# Power_Supply.net
KiCad netlist of a schematic drawn in Altium Designer
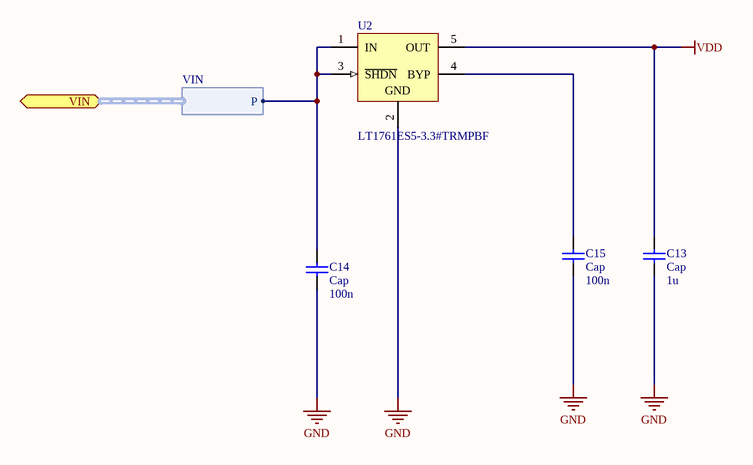
[diagram p0: Power Supply.SchDoc]

(export (version "E")
  (design (tool "Eeschema 10.0.6"))
  (components
    (comp (ref "C13")
      (value "Cap")
      (footprint "RAD-0.3")
      (description "Capacitor")
      (fields (field (name "ALTIUM_VALUE") "1u") (field (name "PUBLISHER") "Altium Limited"))
      (libsource (lib "Miscellaneous Devices") (part "Cap"))
    )
    (comp (ref "C14")
      (value "Cap")
      (footprint "RAD-0.3")
      (description "Capacitor")
      (fields (field (name "ALTIUM_VALUE") "100n") (field (name "PUBLISHER") "Altium Limited"))
      (libsource (lib "Miscellaneous Devices") (part "Cap"))
    )
    (comp (ref "C15")
      (value "Cap")
      (footprint "RAD-0.3")
      (description "Capacitor")
      (fields (field (name "ALTIUM_VALUE") "100n") (field (name "PUBLISHER") "Altium Limited"))
      (libsource (lib "Miscellaneous Devices") (part "Cap"))
    )
    (comp (ref "U2")
      (value "LT1761ES5-3.3#TRMPBF")
      (footprint "LT-S5-5-TSOT-23_N")
      (fields (field (name "MANUFACTURER") "Linear Technology"))
      (libsource (lib "Altium Content Vault") (part "CMP-0476-01224-1"))
    )
  )
  (nets
    (net (code "3") (name "GND") (class "Default")
      (node (ref "C13") (pin "1") (pinfunction "1_1") (pintype "passive"))
      (node (ref "C14") (pin "1") (pinfunction "1_1") (pintype "passive"))
      (node (ref "C15") (pin "1") (pinfunction "1_1") (pintype "passive"))
      (node (ref "U2") (pin "2") (pinfunction "GND_2") (pintype "power_in"))
    )
    (net (code "4") (name "Net-(U2-BYP)") (class "Default")
      (node (ref "C15") (pin "2") (pinfunction "2_2") (pintype "passive"))
      (node (ref "U2") (pin "4") (pinfunction "BYP_4") (pintype "passive"))
    )
    (net (code "5") (name "Net-(U2-IN)") (class "Default")
      (node (ref "C14") (pin "2") (pinfunction "2_2") (pintype "passive"))
      (node (ref "U2") (pin "1") (pinfunction "IN_1") (pintype "power_in"))
      (node (ref "U2") (pin "3") (pinfunction "~{SHDN}_3") (pintype "input"))
    )
    (net (code "6") (name "VDD") (class "Default")
      (node (ref "C13") (pin "2") (pinfunction "2_2") (pintype "passive"))
      (node (ref "U2") (pin "5") (pinfunction "OUT_5") (pintype "power_in"))
    )
  )
)
